# RVP_OVP_HC.net
KiCad netlist of a schematic drawn in Altium Designer
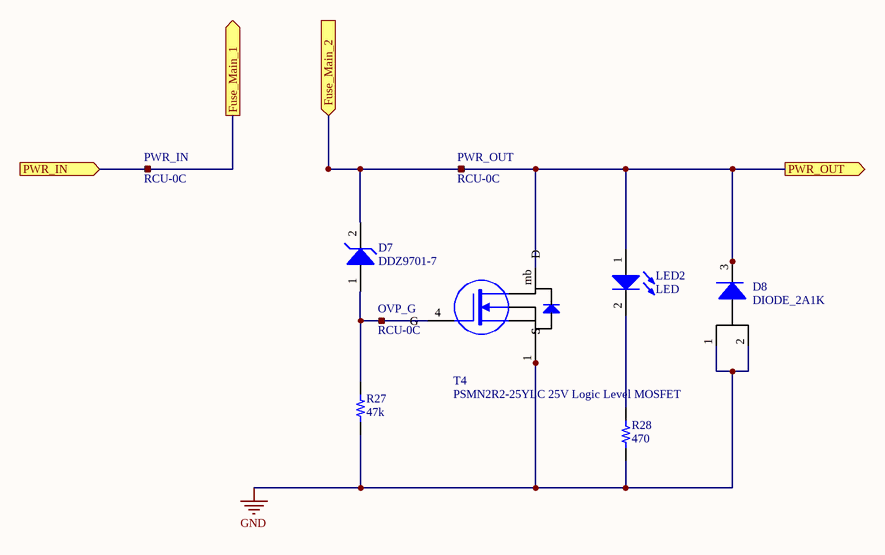
[diagram p0: RVP_OVP_HC.SchDoc]

(export (version "E")
  (design (tool "Eeschema 10.0.6"))
  (components
    (comp (ref "D7")
      (value "DDZ9701-7")
      (footprint "SOD123F")
      (description "Zener Diode 14V 500mW ±5% Surface Mount SOD-123")
      (fields (field (name "POWER") "500mW"))
      (libsource (lib "Altium-Lib") (part "Zener"))
    )
    (comp (ref "D8")
      (value "DIODE_2A1K")
      (footprint "TO-277")
      (fields (field (name "MFRPARTNO") "FSV20100V"))
      (libsource (lib "Altium-Lib") (part "DIODE_2A1K"))
    )
    (comp (ref "LED2") (value "LED") (footprint "0805_LED") (libsource (lib "Altium-Lib") (part "LED")))
    (comp (ref "OVP_G") (value "RCU-0C") (footprint "RCU-0C") (libsource (lib "Altium-Lib") (part "RCU-0C")))
    (comp (ref "PWR_IN") (value "RCU-0C") (footprint "RCU-0C") (libsource (lib "Altium-Lib") (part "RCU-0C")))
    (comp (ref "PWR_OUT")
      (value "RCU-0C")
      (footprint "RCU-0C")
      (libsource (lib "Altium-Lib") (part "RCU-0C"))
    )
    (comp (ref "R27")
      (value "47k")
      (footprint "RES 0805/2012")
      (fields
        (field (name "TOLERANCE") "1%")
        (field (name "POWER") "1/10W")
        (field (name "Comment") "Resistor 47k 0805 1/10W 1%")
        (field (name "CREATED_BY") "Nick Mah")
      )
      (libsource (lib "Altium-Lib") (part "Resistor"))
    )
    (comp (ref "R28")
      (value "470")
      (footprint "RES 0805/2012")
      (fields
        (field (name "TOLERANCE") "1%")
        (field (name "POWER") "1/10W")
        (field (name "Comment") "Resistor 470 0805 1/10W 1%")
        (field (name "CREATED_BY") "Nick Mah")
      )
      (libsource (lib "Altium-Lib") (part "Resistor"))
    )
    (comp (ref "T4")
      (value "PSMN2R2-25YLC 25V Logic Level MOSFET")
      (footprint "LFPAK-SO8")
      (description "N-Channel 25V 100A (Tc) 106W (Tc) Surface Mount LFPAK56, Power-SO8")
      (fields (field (name "MFRPARTNO") "PSMN2R2-25YLC,115") (field (name "CREATED_BY") "Nick"))
      (libsource (lib "Altium-Lib") (part "PSMN2R2-25YLC 25V Logic Level MOSFET"))
    )
  )
  (nets
    (net (code "1") (name "/Fuse_Main_1") (class "Default")
      (node (ref "PWR_IN") (pin "1") (pintype "passive"))
    )
    (net (code "2") (name "/Fuse_Main_2") (class "Default")
      (node (ref "D7") (pin "2") (pinfunction "K_2") (pintype "passive"))
      (node (ref "D8") (pin "3") (pinfunction "K_3") (pintype "passive"))
      (node (ref "LED2") (pin "1") (pinfunction "A_1") (pintype "passive"))
      (node (ref "PWR_OUT") (pin "1") (pintype "passive"))
      (node (ref "T4") (pin "mb") (pinfunction "D_mb") (pintype "passive"))
    )
    (net (code "3") (name "GND") (class "Default")
      (node (ref "D8") (pin "1") (pinfunction "A1_1") (pintype "passive"))
      (node (ref "D8") (pin "2") (pinfunction "A2_2") (pintype "passive"))
      (node (ref "R27") (pin "1") (pinfunction "1_1") (pintype "passive"))
      (node (ref "R28") (pin "1") (pinfunction "1_1") (pintype "passive"))
      (node (ref "T4") (pin "1") (pinfunction "S_1") (pintype "passive"))
      (node (ref "T4") (pin "2") (pinfunction "S_2") (pintype "passive"))
      (node (ref "T4") (pin "3") (pinfunction "S_3") (pintype "passive"))
    )
    (net (code "4") (name "Net-(D7-A)") (class "Default")
      (node (ref "D7") (pin "1") (pinfunction "A_1") (pintype "passive"))
      (node (ref "OVP_G") (pin "1") (pintype "passive"))
      (node (ref "R27") (pin "2") (pinfunction "2_2") (pintype "passive"))
      (node (ref "T4") (pin "4") (pinfunction "G_4") (pintype "passive"))
    )
    (net (code "5") (name "Net-(LED2-K)") (class "Default")
      (node (ref "LED2") (pin "2") (pinfunction "K_2") (pintype "passive"))
      (node (ref "R28") (pin "2") (pinfunction "2_2") (pintype "passive"))
    )
  )
)
